# 0216-carrier-class-d-3w.net
KiCad netlist of a schematic drawn in EAGLE
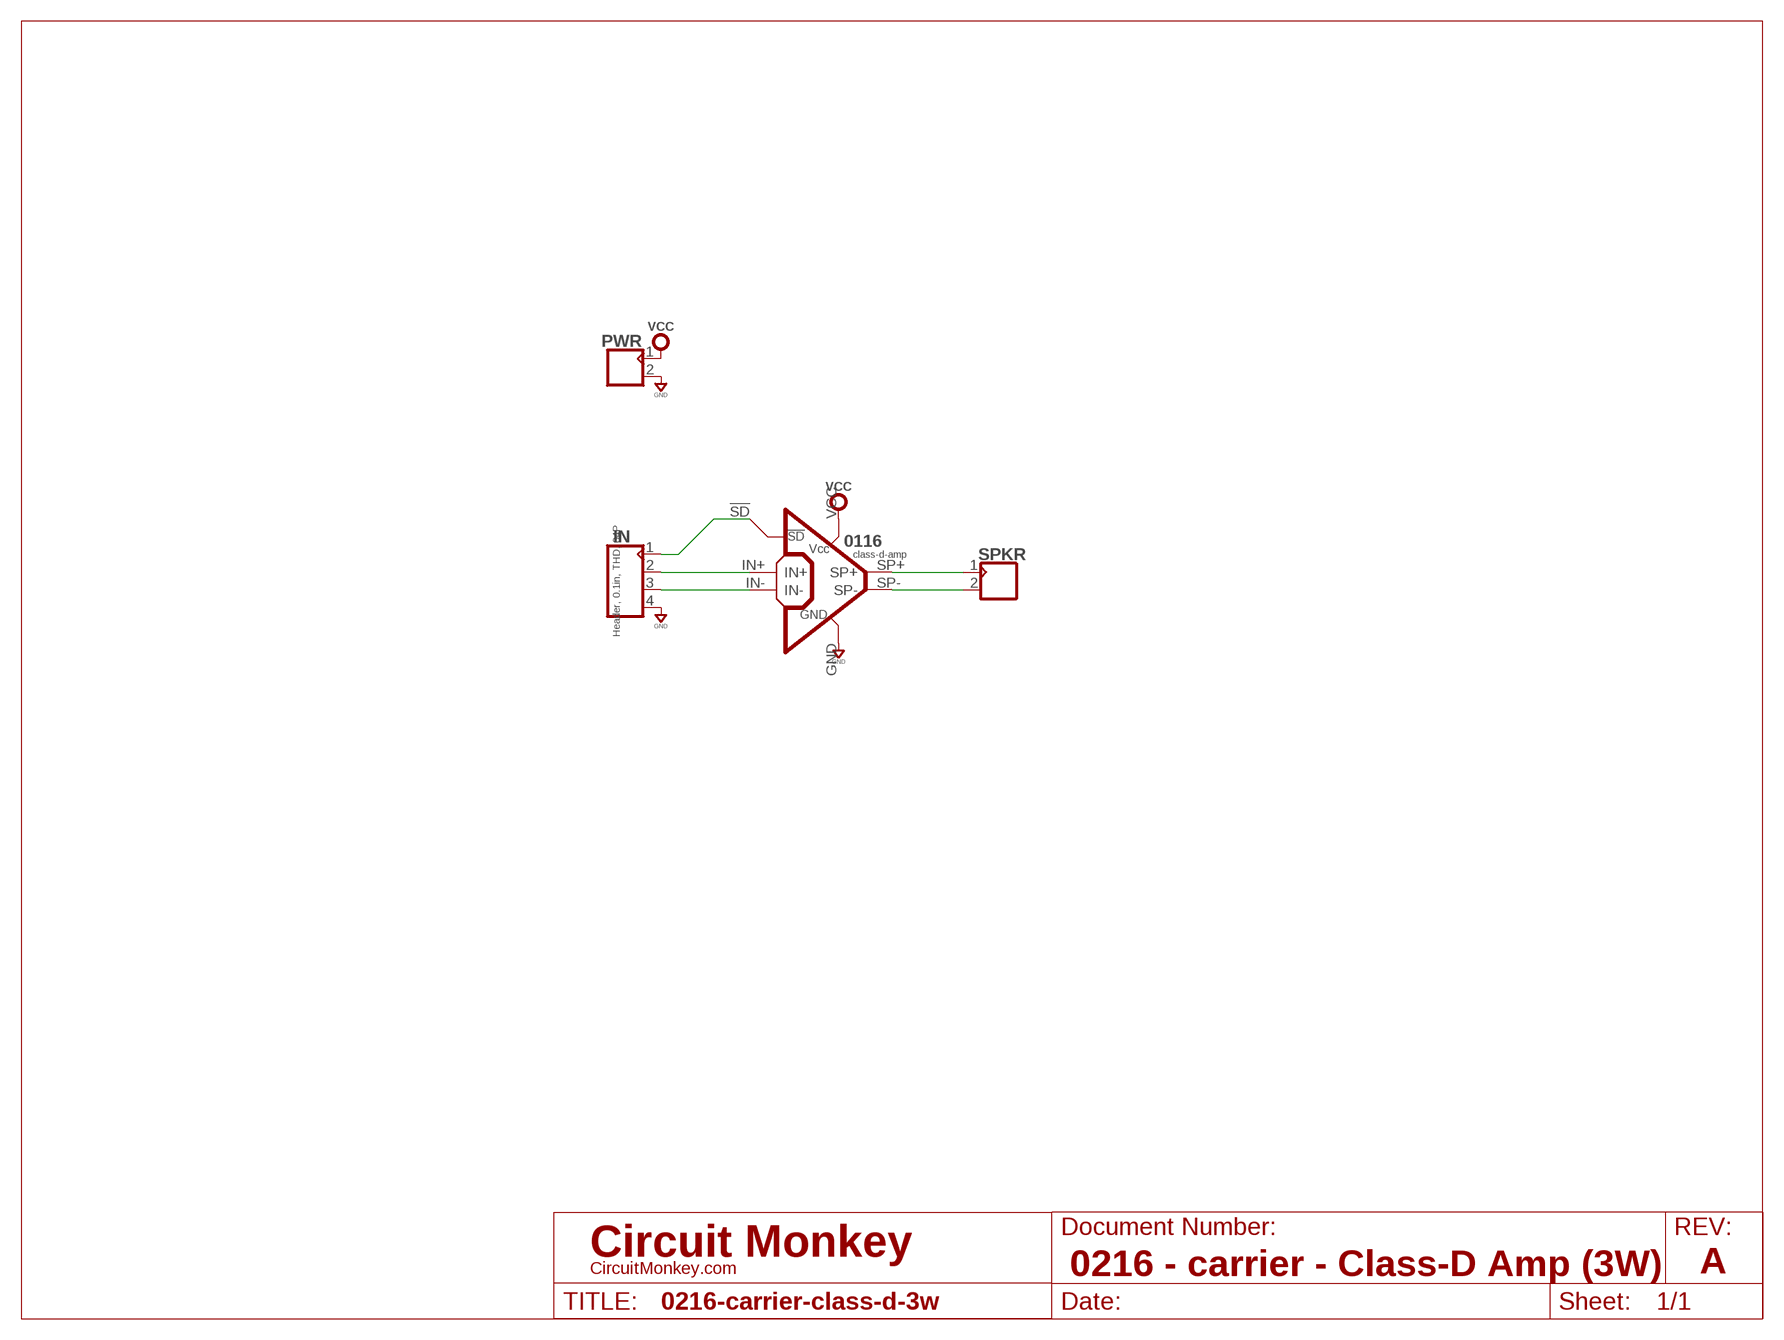
[diagram p0: schematic, sheet 1]

(export (version "E")
  (design (tool "Eeschema 10.0.6"))
  (components
    (comp (ref "0116")
      (value "class-d-amp")
      (footprint "eagle-import:0116A")
      (fields (field (name "MFR") "Circuit Monkey") (field (name "MPN") "0116A"))
      (libsource (lib "eagle-import") (part "0116REV-A"))
    )
    (comp (ref "IN")
      (value "Header, 0.1in, THD, 04P")
      (footprint "eagle-import:MA04X1-VT-THD")
      (fields (field (name "MFR") "Molex") (field (name "MPN") "022284043"))
      (libsource (lib "eagle-import") (part "CON_04X1-THD-VT"))
    )
    (comp (ref "PWR")
      (value "CON_02X1-2.54MM-THD-VT")
      (footprint "eagle-import:MA02X1-VT-THD")
      (libsource (lib "eagle-import") (part "CON_02X1-2.54MM-THD-VT"))
    )
    (comp (ref "SPKR")
      (value "CON_02X1-2.54MM-THD-VT")
      (footprint "eagle-import:MA02X1-VT-THD")
      (libsource (lib "eagle-import") (part "CON_02X1-2.54MM-THD-VT"))
    )
  )
  (nets
    (net (code "1") (name "GND") (class "Default")
      (node (ref "0116") (pin "GND") (pinfunction "GND_GND") (pintype "bidirectional"))
      (node (ref "IN") (pin "4") (pinfunction "4_4") (pintype "passive"))
      (node (ref "PWR") (pin "2") (pinfunction "2_2") (pintype "passive"))
    )
    (net (code "2") (name "Net-(0116-PadIN+)") (class "Default")
      (node (ref "0116") (pin "IN+") (pinfunction "IN+_IN+") (pintype "bidirectional"))
      (node (ref "IN") (pin "2") (pinfunction "2_2") (pintype "passive"))
    )
    (net (code "3") (name "Net-(0116-PadIN-)") (class "Default")
      (node (ref "0116") (pin "IN-") (pinfunction "IN-_IN-") (pintype "bidirectional"))
      (node (ref "IN") (pin "3") (pinfunction "3_3") (pintype "passive"))
    )
    (net (code "4") (name "Net-(0116-PadSP+)") (class "Default")
      (node (ref "0116") (pin "SP+") (pinfunction "SP+_SP+") (pintype "bidirectional"))
      (node (ref "SPKR") (pin "1") (pinfunction "1_1") (pintype "passive"))
    )
    (net (code "5") (name "Net-(0116-PadSP-)") (class "Default")
      (node (ref "0116") (pin "SP-") (pinfunction "SP-_SP-") (pintype "bidirectional"))
      (node (ref "SPKR") (pin "2") (pinfunction "2_2") (pintype "passive"))
    )
    (net (code "6") (name "Net-(0116-~{SD})") (class "Default")
      (node (ref "0116") (pin "!SD") (pinfunction "~{SD}_!SD") (pintype "bidirectional"))
      (node (ref "IN") (pin "1") (pinfunction "1_1") (pintype "passive"))
    )
    (net (code "7") (name "VCC") (class "Default")
      (node (ref "0116") (pin "VCC") (pinfunction "VCC_VCC") (pintype "bidirectional"))
      (node (ref "PWR") (pin "1") (pinfunction "1_1") (pintype "passive"))
    )
  )
)
